# Sheet1.net
KiCad netlist of a schematic drawn in Altium Designer
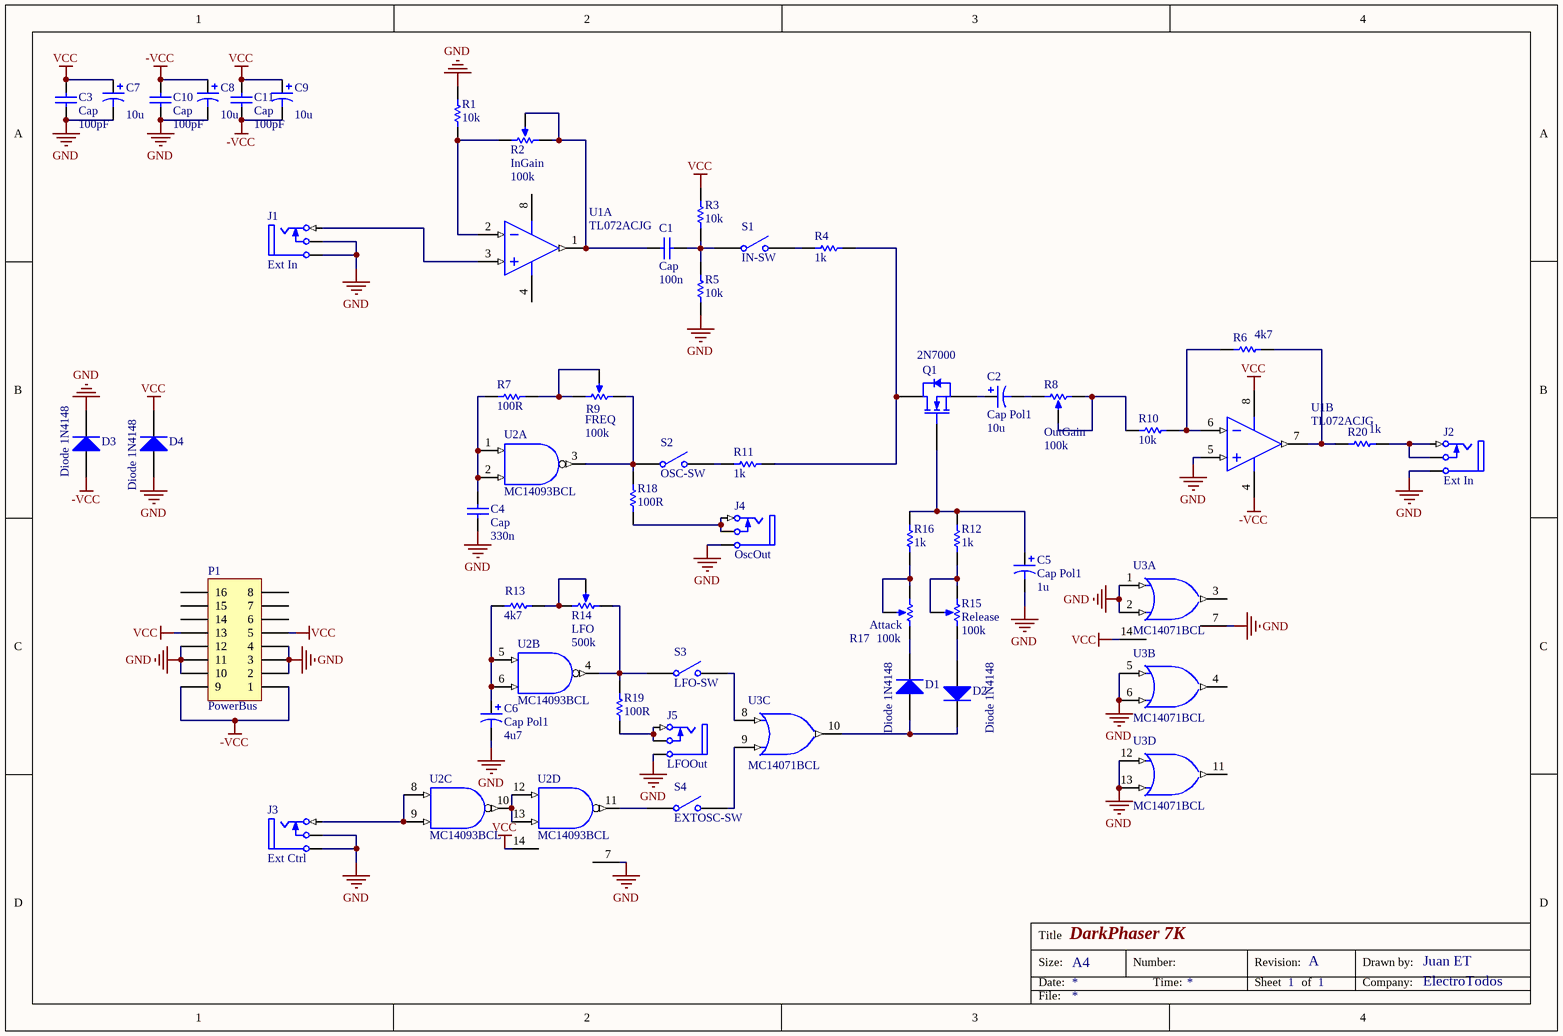
[diagram p0: Sheet1.SchDoc]

(export (version "E")
  (design (tool "Eeschema 10.0.6"))
  (components
    (comp (ref "C1")
      (value "Cap")
      (footprint "RAD-0.1")
      (description "Capacitor")
      (fields (field (name "ALTIUM_VALUE") "100n") (field (name "PUBLISHER") "Altium Limited"))
      (libsource (lib "Miscellaneous Devices") (part "Cap"))
    )
    (comp (ref "C2")
      (value "Cap Pol1")
      (footprint "Cap Radial")
      (description "Polarized Capacitor (Radial)")
      (fields (field (name "ALTIUM_VALUE") "10u") (field (name "PUBLISHER") "Altium Limited"))
      (libsource (lib "Miscellaneous Devices") (part "Cap Pol1"))
    )
    (comp (ref "C3")
      (value "Cap")
      (footprint "RAD-0.1")
      (description "Capacitor")
      (fields (field (name "ALTIUM_VALUE") "100pF") (field (name "PUBLISHER") "Altium Limited"))
      (libsource (lib "Miscellaneous Devices") (part "Cap"))
    )
    (comp (ref "C4")
      (value "Cap")
      (footprint "RAD-0.1")
      (description "Capacitor")
      (fields (field (name "ALTIUM_VALUE") "330n") (field (name "PUBLISHER") "Altium Limited"))
      (libsource (lib "Miscellaneous Devices") (part "Cap"))
    )
    (comp (ref "C5")
      (value "Cap Pol1")
      (footprint "Cap Radial")
      (description "Polarized Capacitor (Radial)")
      (fields (field (name "ALTIUM_VALUE") "1u") (field (name "PUBLISHER") "Altium Limited"))
      (libsource (lib "Miscellaneous Devices") (part "Cap Pol1"))
    )
    (comp (ref "C6")
      (value "Cap Pol1")
      (footprint "Cap Radial")
      (description "Polarized Capacitor (Radial)")
      (fields (field (name "ALTIUM_VALUE") "4u7") (field (name "PUBLISHER") "Altium Limited"))
      (libsource (lib "Miscellaneous Devices") (part "Cap Pol1"))
    )
    (comp (ref "C7")
      (value "10u")
      (footprint "Cap Radial")
      (description "Polarized Capacitor (Radial)")
      (fields (field (name "Comment") "Cap Pol1") (field (name "PUBLISHER") "Altium Limited"))
      (libsource (lib "Miscellaneous Devices") (part "Cap Pol1"))
    )
    (comp (ref "C8")
      (value "10u")
      (footprint "Cap Radial")
      (description "Polarized Capacitor (Radial)")
      (fields (field (name "Comment") "Cap Pol1") (field (name "PUBLISHER") "Altium Limited"))
      (libsource (lib "Miscellaneous Devices") (part "Cap Pol1"))
    )
    (comp (ref "C9")
      (value "10u")
      (footprint "Cap Radial")
      (description "Polarized Capacitor (Radial)")
      (fields (field (name "Comment") "Cap Pol1") (field (name "PUBLISHER") "Altium Limited"))
      (libsource (lib "Miscellaneous Devices") (part "Cap Pol1"))
    )
    (comp (ref "C10")
      (value "Cap")
      (footprint "RAD-0.1")
      (description "Capacitor")
      (fields (field (name "ALTIUM_VALUE") "100pF") (field (name "PUBLISHER") "Altium Limited"))
      (libsource (lib "Miscellaneous Devices") (part "Cap"))
    )
    (comp (ref "C11")
      (value "Cap")
      (footprint "RAD-0.1")
      (description "Capacitor")
      (fields (field (name "ALTIUM_VALUE") "100pF") (field (name "PUBLISHER") "Altium Limited"))
      (libsource (lib "Miscellaneous Devices") (part "Cap"))
    )
    (comp (ref "D1")
      (value "Diode 1N4148")
      (footprint "DO-35")
      (description "High Conductance Fast Diode")
      (fields (field (name "PUBLISHER") "Altium Limited"))
      (libsource (lib "Miscellaneous Devices") (part "Diode 1N4148"))
    )
    (comp (ref "D2")
      (value "Diode 1N4148")
      (footprint "DO-35")
      (description "High Conductance Fast Diode")
      (fields (field (name "PUBLISHER") "Altium Limited"))
      (libsource (lib "Miscellaneous Devices") (part "Diode 1N4148"))
    )
    (comp (ref "D3")
      (value "Diode 1N4148")
      (footprint "DO-35")
      (description "High Conductance Fast Diode")
      (fields (field (name "PUBLISHER") "Altium Limited"))
      (libsource (lib "Miscellaneous Devices") (part "Diode 1N4148"))
    )
    (comp (ref "D4")
      (value "Diode 1N4148")
      (footprint "DO-35")
      (description "High Conductance Fast Diode")
      (fields (field (name "PUBLISHER") "Altium Limited"))
      (libsource (lib "Miscellaneous Devices") (part "Diode 1N4148"))
    )
    (comp (ref "J1")
      (value "Ext In")
      (footprint "HDR1X3")
      (description "Jack Socket, 1/4\" [6.5mm], Thru-Hole, Vertical, 2-Conductor with Tip closed")
      (fields (field (name "PUBLISHER") "Altium Limited"))
      (libsource (lib "Miscellaneous Connectors") (part "Phonejack2 TN"))
    )
    (comp (ref "J2")
      (value "Ext In")
      (footprint "HDR1X3")
      (description "Jack Socket, 1/4\" [6.5mm], Thru-Hole, Vertical, 2-Conductor with Tip closed")
      (fields (field (name "PUBLISHER") "Altium Limited"))
      (libsource (lib "Miscellaneous Connectors") (part "Phonejack2 TN"))
    )
    (comp (ref "J3")
      (value "Ext Ctrl")
      (footprint "HDR1X3")
      (description "Jack Socket, 1/4\" [6.5mm], Thru-Hole, Vertical, 2-Conductor with Tip closed")
      (fields (field (name "PUBLISHER") "Altium Limited"))
      (libsource (lib "Miscellaneous Connectors") (part "Phonejack2 TN"))
    )
    (comp (ref "J4")
      (value "OscOut")
      (footprint "HDR1X3")
      (description "Jack Socket, 1/4\" [6.5mm], Thru-Hole, Vertical, 2-Conductor with Tip closed")
      (fields (field (name "PUBLISHER") "Altium Limited"))
      (libsource (lib "Miscellaneous Connectors") (part "Phonejack2 TN"))
    )
    (comp (ref "J5")
      (value "LFOOut")
      (footprint "HDR1X3")
      (description "Jack Socket, 1/4\" [6.5mm], Thru-Hole, Vertical, 2-Conductor with Tip closed")
      (fields (field (name "PUBLISHER") "Altium Limited"))
      (libsource (lib "Miscellaneous Connectors") (part "Phonejack2 TN"))
    )
    (comp (ref "P1")
      (value "PowerBus")
      (footprint "HDR2X8_CEN")
      (description "Header, 8-Pin, Dual row")
      (fields (field (name "PUBLISHER") "Altium Limited"))
      (libsource (lib "Miscellaneous Connectors") (part "Header 8X2A"))
    )
    (comp (ref "Q1")
      (value "2N7000")
      (footprint "SOT54")
      (description "N-channel Enhancement Mode Field-effect Transistor")
      (fields (field (name "PUBLISHER") "Altium Limited"))
      (libsource (lib "Philips Discrete MOSFET - Low Power") (part "2N7000"))
    )
    (comp (ref "R1")
      (value "10k")
      (footprint "AXIAL-0.3")
      (description "Resistor")
      (fields (field (name "PUBLISHER") "Altium Limited"))
      (libsource (lib "Miscellaneous Devices") (part "Res1"))
    )
    (comp (ref "R2")
      (value "InGain")
      (footprint "HDR1X3")
      (description "Potentiometer")
      (fields (field (name "ALTIUM_VALUE") "100k") (field (name "PUBLISHER") "Altium Limited"))
      (libsource (lib "Miscellaneous Devices") (part "RPot"))
    )
    (comp (ref "R3")
      (value "10k")
      (footprint "AXIAL-0.3")
      (description "Resistor")
      (fields (field (name "PUBLISHER") "Altium Limited"))
      (libsource (lib "Miscellaneous Devices") (part "Res1"))
    )
    (comp (ref "R4")
      (value "1k")
      (footprint "AXIAL-0.3")
      (description "Resistor")
      (fields (field (name "PUBLISHER") "Altium Limited"))
      (libsource (lib "Miscellaneous Devices") (part "Res1"))
    )
    (comp (ref "R5")
      (value "10k")
      (footprint "AXIAL-0.3")
      (description "Resistor")
      (fields (field (name "PUBLISHER") "Altium Limited"))
      (libsource (lib "Miscellaneous Devices") (part "Res1"))
    )
    (comp (ref "R6")
      (value "4k7")
      (footprint "AXIAL-0.3")
      (description "Resistor")
      (fields (field (name "PUBLISHER") "Altium Limited"))
      (libsource (lib "Miscellaneous Devices") (part "Res1"))
    )
    (comp (ref "R7")
      (value "100R")
      (footprint "AXIAL-0.3")
      (description "Resistor")
      (fields (field (name "PUBLISHER") "Altium Limited"))
      (libsource (lib "Miscellaneous Devices") (part "Res1"))
    )
    (comp (ref "R8")
      (value "OutGain")
      (footprint "HDR1X3")
      (description "Potentiometer")
      (fields (field (name "ALTIUM_VALUE") "100k") (field (name "PUBLISHER") "Altium Limited"))
      (libsource (lib "Miscellaneous Devices") (part "RPot"))
    )
    (comp (ref "R9")
      (value "FREQ")
      (footprint "HDR1X3")
      (description "Potentiometer")
      (fields (field (name "ALTIUM_VALUE") "100k") (field (name "PUBLISHER") "Altium Limited"))
      (libsource (lib "Miscellaneous Devices") (part "RPot"))
    )
    (comp (ref "R10")
      (value "10k")
      (footprint "AXIAL-0.3")
      (description "Resistor")
      (fields (field (name "PUBLISHER") "Altium Limited"))
      (libsource (lib "Miscellaneous Devices") (part "Res1"))
    )
    (comp (ref "R11")
      (value "1k")
      (footprint "AXIAL-0.3")
      (description "Resistor")
      (fields (field (name "PUBLISHER") "Altium Limited"))
      (libsource (lib "Miscellaneous Devices") (part "Res1"))
    )
    (comp (ref "R12")
      (value "1k")
      (footprint "AXIAL-0.3")
      (description "Resistor")
      (fields (field (name "PUBLISHER") "Altium Limited"))
      (libsource (lib "Miscellaneous Devices") (part "Res1"))
    )
    (comp (ref "R13")
      (value "4k7")
      (footprint "AXIAL-0.3")
      (description "Resistor")
      (fields (field (name "PUBLISHER") "Altium Limited"))
      (libsource (lib "Miscellaneous Devices") (part "Res1"))
    )
    (comp (ref "R14")
      (value "LFO")
      (footprint "HDR1X3")
      (description "Potentiometer")
      (fields (field (name "ALTIUM_VALUE") "500k") (field (name "PUBLISHER") "Altium Limited"))
      (libsource (lib "Miscellaneous Devices") (part "RPot"))
    )
    (comp (ref "R15")
      (value "Release")
      (footprint "HDR1X3")
      (description "Potentiometer")
      (fields (field (name "ALTIUM_VALUE") "100k") (field (name "PUBLISHER") "Altium Limited"))
      (libsource (lib "Miscellaneous Devices") (part "RPot"))
    )
    (comp (ref "R16")
      (value "1k")
      (footprint "AXIAL-0.3")
      (description "Resistor")
      (fields (field (name "PUBLISHER") "Altium Limited"))
      (libsource (lib "Miscellaneous Devices") (part "Res1"))
    )
    (comp (ref "R17")
      (value "Attack")
      (footprint "HDR1X3")
      (description "Potentiometer")
      (fields (field (name "ALTIUM_VALUE") "100k") (field (name "PUBLISHER") "Altium Limited"))
      (libsource (lib "Miscellaneous Devices") (part "RPot"))
    )
    (comp (ref "R18")
      (value "100R")
      (footprint "AXIAL-0.3")
      (description "Resistor")
      (fields (field (name "PUBLISHER") "Altium Limited"))
      (libsource (lib "Miscellaneous Devices") (part "Res1"))
    )
    (comp (ref "R19")
      (value "100R")
      (footprint "AXIAL-0.3")
      (description "Resistor")
      (fields (field (name "PUBLISHER") "Altium Limited"))
      (libsource (lib "Miscellaneous Devices") (part "Res1"))
    )
    (comp (ref "R20")
      (value "1k")
      (footprint "AXIAL-0.3")
      (description "Resistor")
      (fields (field (name "PUBLISHER") "Altium Limited"))
      (libsource (lib "Miscellaneous Devices") (part "Res1"))
    )
    (comp (ref "S1")
      (value "IN-SW")
      (footprint "PIN2")
      (description "Single-Pole, Single-Throw Switch")
      (fields (field (name "PUBLISHER") "Altium Limited"))
      (libsource (lib "Miscellaneous Devices") (part "SW-SPST"))
    )
    (comp (ref "S2")
      (value "OSC-SW")
      (footprint "PIN2")
      (description "Single-Pole, Single-Throw Switch")
      (fields (field (name "PUBLISHER") "Altium Limited"))
      (libsource (lib "Miscellaneous Devices") (part "SW-SPST"))
    )
    (comp (ref "S3")
      (value "LFO-SW")
      (footprint "PIN2")
      (description "Single-Pole, Single-Throw Switch")
      (fields (field (name "PUBLISHER") "Altium Limited"))
      (libsource (lib "Miscellaneous Devices") (part "SW-SPST"))
    )
    (comp (ref "S4")
      (value "EXTOSC-SW")
      (footprint "PIN2")
      (description "Single-Pole, Single-Throw Switch")
      (fields (field (name "PUBLISHER") "Altium Limited"))
      (libsource (lib "Miscellaneous Devices") (part "SW-SPST"))
    )
    (comp (ref "U1")
      (value "TL072ACJG")
      (footprint "693-02")
      (description "Low-Noise JFET-Input Operational Amplifier")
      (fields (field (name "PUBLISHER") "Altium Limited"))
      (libsource (lib "Motorola Amplifier Operational Amplifier") (part "TL072ACJG"))
    )
    (comp (ref "U2")
      (value "MC14093BCL")
      (footprint "632-08")
      (description "Quad 2-Input NAND Schmitt Trigger")
      (fields (field (name "PUBLISHER") "Altium Limited"))
      (libsource (lib "ON Semi Logic Gate") (part "MC14093BCL"))
    )
    (comp (ref "U3")
      (value "MC14071BCL")
      (footprint "632-08")
      (description "Quad 2-Input OR Gate")
      (fields (field (name "PUBLISHER") "Altium Limited"))
      (libsource (lib "ON Semi Logic Gate") (part "MC14071BCL"))
    )
  )
  (nets
    (net (code "1") (name "-VCC") (class "Default")
      (node (ref "C10") (pin "2") (pinfunction "2_2") (pintype "passive"))
      (node (ref "C11") (pin "1") (pinfunction "1_1") (pintype "passive"))
      (node (ref "C8") (pin "1") (pinfunction "1_1") (pintype "passive"))
      (node (ref "C9") (pin "2") (pinfunction "2_2") (pintype "passive"))
      (node (ref "D3") (pin "1") (pinfunction "A_1") (pintype "passive"))
      (node (ref "P1") (pin "1") (pinfunction "1_1") (pintype "passive"))
      (node (ref "P1") (pin "9") (pinfunction "9_9") (pintype "passive"))
      (node (ref "U1") (pin "4") (pinfunction "V-_4") (pintype "power_in"))
    )
    (net (code "2") (name "GND") (class "Default")
      (node (ref "C10") (pin "1") (pinfunction "1_1") (pintype "passive"))
      (node (ref "C3") (pin "2") (pinfunction "2_2") (pintype "passive"))
      (node (ref "C4") (pin "1") (pinfunction "1_1") (pintype "passive"))
      (node (ref "C5") (pin "2") (pinfunction "2_2") (pintype "passive"))
      (node (ref "C6") (pin "2") (pinfunction "2_2") (pintype "passive"))
      (node (ref "C7") (pin "2") (pinfunction "2_2") (pintype "passive"))
      (node (ref "C8") (pin "2") (pinfunction "2_2") (pintype "passive"))
      (node (ref "D3") (pin "2") (pinfunction "K_2") (pintype "passive"))
      (node (ref "D4") (pin "1") (pinfunction "A_1") (pintype "passive"))
      (node (ref "J1") (pin "2") (pinfunction "TN_2") (pintype "passive"))
      (node (ref "J1") (pin "5") (pinfunction "S_5") (pintype "power_in"))
      (node (ref "J2") (pin "5") (pinfunction "S_5") (pintype "power_in"))
      (node (ref "J3") (pin "2") (pinfunction "TN_2") (pintype "passive"))
      (node (ref "J3") (pin "5") (pinfunction "S_5") (pintype "power_in"))
      (node (ref "J4") (pin "5") (pinfunction "S_5") (pintype "power_in"))
      (node (ref "J5") (pin "5") (pinfunction "S_5") (pintype "power_in"))
      (node (ref "P1") (pin "10") (pinfunction "10_10") (pintype "passive"))
      (node (ref "P1") (pin "11") (pinfunction "11_11") (pintype "passive"))
      (node (ref "P1") (pin "12") (pinfunction "12_12") (pintype "passive"))
      (node (ref "P1") (pin "2") (pinfunction "2_2") (pintype "passive"))
      (node (ref "P1") (pin "3") (pinfunction "3_3") (pintype "passive"))
      (node (ref "P1") (pin "4") (pinfunction "4_4") (pintype "passive"))
      (node (ref "R1") (pin "2") (pinfunction "2_2") (pintype "passive"))
      (node (ref "R5") (pin "2") (pinfunction "2_2") (pintype "passive"))
      (node (ref "U1") (pin "5") (pinfunction "IN+_5") (pintype "input"))
      (node (ref "U2") (pin "7") (pinfunction "GND_7") (pintype "power_in"))
      (node (ref "U3") (pin "1") (pinfunction "A_1") (pintype "input"))
      (node (ref "U3") (pin "12") (pinfunction "A_12") (pintype "input"))
      (node (ref "U3") (pin "13") (pinfunction "B_13") (pintype "input"))
      (node (ref "U3") (pin "2") (pinfunction "B_2") (pintype "input"))
      (node (ref "U3") (pin "5") (pinfunction "A_5") (pintype "input"))
      (node (ref "U3") (pin "6") (pinfunction "B_6") (pintype "input"))
      (node (ref "U3") (pin "7") (pinfunction "GND_7") (pintype "power_in"))
    )
    (net (code "3") (name "Net-(D1-A)") (class "Default")
      (node (ref "D1") (pin "1") (pinfunction "A_1") (pintype "passive"))
      (node (ref "D2") (pin "2") (pinfunction "K_2") (pintype "passive"))
      (node (ref "U3") (pin "10") (pinfunction "Y_10") (pintype "output"))
    )
    (net (code "4") (name "Net-(D1-K)") (class "Default")
      (node (ref "D1") (pin "2") (pinfunction "K_2") (pintype "passive"))
      (node (ref "R17") (pin "2") (pinfunction "BOT_2") (pintype "passive"))
    )
    (net (code "5") (name "Net-(D2-A)") (class "Default")
      (node (ref "D2") (pin "1") (pinfunction "A_1") (pintype "passive"))
      (node (ref "R15") (pin "2") (pinfunction "BOT_2") (pintype "passive"))
    )
    (net (code "6") (name "Net-(J1-T)") (class "Default")
      (node (ref "J1") (pin "1") (pinfunction "T_1") (pintype "input"))
      (node (ref "U1") (pin "3") (pinfunction "IN+_3") (pintype "input"))
    )
    (net (code "7") (name "Net-(J2-T)") (class "Default")
      (node (ref "J2") (pin "1") (pinfunction "T_1") (pintype "input"))
      (node (ref "J2") (pin "2") (pinfunction "TN_2") (pintype "passive"))
      (node (ref "R20") (pin "1") (pinfunction "1_1") (pintype "passive"))
    )
    (net (code "8") (name "Net-(J3-T)") (class "Default")
      (node (ref "J3") (pin "1") (pinfunction "T_1") (pintype "input"))
      (node (ref "U2") (pin "8") (pinfunction "A_8") (pintype "input"))
      (node (ref "U2") (pin "9") (pinfunction "B_9") (pintype "input"))
    )
    (net (code "9") (name "Net-(J4-T)") (class "Default")
      (node (ref "J4") (pin "1") (pinfunction "T_1") (pintype "input"))
      (node (ref "J4") (pin "2") (pinfunction "TN_2") (pintype "passive"))
      (node (ref "R18") (pin "1") (pinfunction "1_1") (pintype "passive"))
    )
    (net (code "10") (name "Net-(J5-T)") (class "Default")
      (node (ref "J5") (pin "1") (pinfunction "T_1") (pintype "input"))
      (node (ref "J5") (pin "2") (pinfunction "TN_2") (pintype "passive"))
      (node (ref "R19") (pin "1") (pinfunction "1_1") (pintype "passive"))
    )
    (net (code "11") (name "Net-(Q1-D)") (class "Default")
      (node (ref "Q1") (pin "1") (pinfunction "D_1") (pintype "passive"))
      (node (ref "R11") (pin "2") (pinfunction "2_2") (pintype "passive"))
      (node (ref "R4") (pin "2") (pinfunction "2_2") (pintype "passive"))
    )
    (net (code "12") (name "Net-(Q1-G)") (class "Default")
      (node (ref "C5") (pin "1") (pinfunction "1_1") (pintype "passive"))
      (node (ref "Q1") (pin "2") (pinfunction "G_2") (pintype "passive"))
      (node (ref "R12") (pin "2") (pinfunction "2_2") (pintype "passive"))
      (node (ref "R16") (pin "2") (pinfunction "2_2") (pintype "passive"))
    )
    (net (code "13") (name "Net-(Q1-S)") (class "Default")
      (node (ref "C2") (pin "1") (pinfunction "1_1") (pintype "passive"))
      (node (ref "Q1") (pin "3") (pinfunction "S_3") (pintype "passive"))
    )
    (net (code "14") (name "Net-(R2-BOT)") (class "Default")
      (node (ref "R1") (pin "1") (pinfunction "1_1") (pintype "passive"))
      (node (ref "R2") (pin "2") (pinfunction "BOT_2") (pintype "passive"))
      (node (ref "U1") (pin "2") (pinfunction "IN-_2") (pintype "input"))
    )
    (net (code "15") (name "Net-(R2-TAP)") (class "Default")
      (node (ref "C1") (pin "2") (pinfunction "2_2") (pintype "passive"))
      (node (ref "R2") (pin "1") (pinfunction "TOP_1") (pintype "passive"))
      (node (ref "R2") (pin "3") (pinfunction "TAP_3") (pintype "passive"))
      (node (ref "U1") (pin "1") (pinfunction "OUT_1") (pintype "output"))
    )
    (net (code "16") (name "Net-(R8-BOT)") (class "Default")
      (node (ref "R10") (pin "2") (pinfunction "2_2") (pintype "passive"))
      (node (ref "R8") (pin "2") (pinfunction "BOT_2") (pintype "passive"))
      (node (ref "R8") (pin "3") (pinfunction "TAP_3") (pintype "passive"))
    )
    (net (code "17") (name "Net-(R8-TOP)") (class "Default")
      (node (ref "C2") (pin "2") (pinfunction "2_2") (pintype "passive"))
      (node (ref "R8") (pin "1") (pinfunction "TOP_1") (pintype "passive"))
    )
    (net (code "18") (name "Net-(R9-BOT)") (class "Default")
      (node (ref "R7") (pin "2") (pinfunction "2_2") (pintype "passive"))
      (node (ref "R9") (pin "2") (pinfunction "BOT_2") (pintype "passive"))
      (node (ref "R9") (pin "3") (pinfunction "TAP_3") (pintype "passive"))
    )
    (net (code "19") (name "Net-(R9-TOP)") (class "Default")
      (node (ref "R18") (pin "2") (pinfunction "2_2") (pintype "passive"))
      (node (ref "R9") (pin "1") (pinfunction "TOP_1") (pintype "passive"))
      (node (ref "S2") (pin "1") (pinfunction "COMMON_1") (pintype "passive"))
      (node (ref "U2") (pin "3") (pinfunction "~{Y}_3") (pintype "output"))
    )
    (net (code "20") (name "Net-(R14-BOT)") (class "Default")
      (node (ref "R13") (pin "2") (pinfunction "2_2") (pintype "passive"))
      (node (ref "R14") (pin "2") (pinfunction "BOT_2") (pintype "passive"))
      (node (ref "R14") (pin "3") (pinfunction "TAP_3") (pintype "passive"))
    )
    (net (code "21") (name "Net-(R14-TOP)") (class "Default")
      (node (ref "R14") (pin "1") (pinfunction "TOP_1") (pintype "passive"))
      (node (ref "R19") (pin "2") (pinfunction "2_2") (pintype "passive"))
      (node (ref "S3") (pin "1") (pinfunction "COMMON_1") (pintype "passive"))
      (node (ref "U2") (pin "4") (pinfunction "~{Y}_4") (pintype "output"))
    )
    (net (code "22") (name "Net-(R15-TAP)") (class "Default")
      (node (ref "R12") (pin "1") (pinfunction "1_1") (pintype "passive"))
      (node (ref "R15") (pin "1") (pinfunction "TOP_1") (pintype "passive"))
      (node (ref "R15") (pin "3") (pinfunction "TAP_3") (pintype "passive"))
    )
    (net (code "23") (name "Net-(R17-TAP)") (class "Default")
      (node (ref "R16") (pin "1") (pinfunction "1_1") (pintype "passive"))
      (node (ref "R17") (pin "1") (pinfunction "TOP_1") (pintype "passive"))
      (node (ref "R17") (pin "3") (pinfunction "TAP_3") (pintype "passive"))
    )
    (net (code "24") (name "Net-(S1-COMMON)") (class "Default")
      (node (ref "C1") (pin "1") (pinfunction "1_1") (pintype "passive"))
      (node (ref "R3") (pin "2") (pinfunction "2_2") (pintype "passive"))
      (node (ref "R5") (pin "1") (pinfunction "1_1") (pintype "passive"))
      (node (ref "S1") (pin "1") (pinfunction "COMMON_1") (pintype "passive"))
    )
    (net (code "25") (name "Net-(S1-NO)") (class "Default")
      (node (ref "R4") (pin "1") (pinfunction "1_1") (pintype "passive"))
      (node (ref "S1") (pin "2") (pinfunction "NO_2") (pintype "passive"))
    )
    (net (code "26") (name "Net-(S2-NO)") (class "Default")
      (node (ref "R11") (pin "1") (pinfunction "1_1") (pintype "passive"))
      (node (ref "S2") (pin "2") (pinfunction "NO_2") (pintype "passive"))
    )
    (net (code "27") (name "Net-(S3-NO)") (class "Default")
      (node (ref "S3") (pin "2") (pinfunction "NO_2") (pintype "passive"))
      (node (ref "U3") (pin "8") (pinfunction "A_8") (pintype "input"))
    )
    (net (code "28") (name "Net-(S4-COMMON)") (class "Default")
      (node (ref "S4") (pin "1") (pinfunction "COMMON_1") (pintype "passive"))
      (node (ref "U2") (pin "11") (pinfunction "~{Y}_11") (pintype "output"))
    )
    (net (code "29") (name "Net-(S4-NO)") (class "Default")
      (node (ref "S4") (pin "2") (pinfunction "NO_2") (pintype "passive"))
      (node (ref "U3") (pin "9") (pinfunction "B_9") (pintype "input"))
    )
    (net (code "30") (name "Net-(U1B-IN-)") (class "Default")
      (node (ref "R10") (pin "1") (pinfunction "1_1") (pintype "passive"))
      (node (ref "R6") (pin "2") (pinfunction "2_2") (pintype "passive"))
      (node (ref "U1") (pin "6") (pinfunction "IN-_6") (pintype "input"))
    )
    (net (code "31") (name "Net-(U1B-OUT)") (class "Default")
      (node (ref "R20") (pin "2") (pinfunction "2_2") (pintype "passive"))
      (node (ref "R6") (pin "1") (pinfunction "1_1") (pintype "passive"))
      (node (ref "U1") (pin "7") (pinfunction "OUT_7") (pintype "output"))
    )
    (net (code "32") (name "Net-(U2A-A)") (class "Default")
      (node (ref "C4") (pin "2") (pinfunction "2_2") (pintype "passive"))
      (node (ref "R7") (pin "1") (pinfunction "1_1") (pintype "passive"))
      (node (ref "U2") (pin "1") (pinfunction "A_1") (pintype "input"))
      (node (ref "U2") (pin "2") (pinfunction "B_2") (pintype "input"))
    )
    (net (code "33") (name "Net-(U2B-A)") (class "Default")
      (node (ref "C6") (pin "1") (pinfunction "1_1") (pintype "passive"))
      (node (ref "R13") (pin "1") (pinfunction "1_1") (pintype "passive"))
      (node (ref "U2") (pin "5") (pinfunction "A_5") (pintype "input"))
      (node (ref "U2") (pin "6") (pinfunction "B_6") (pintype "input"))
    )
    (net (code "34") (name "Net-(U2C-~{Y})") (class "Default")
      (node (ref "U2") (pin "10") (pinfunction "~{Y}_10") (pintype "output"))
      (node (ref "U2") (pin "12") (pinfunction "A_12") (pintype "input"))
      (node (ref "U2") (pin "13") (pinfunction "B_13") (pintype "input"))
    )
    (net (code "35") (name "VCC") (class "Default")
      (node (ref "C11") (pin "2") (pinfunction "2_2") (pintype "passive"))
      (node (ref "C3") (pin "1") (pinfunction "1_1") (pintype "passive"))
      (node (ref "C7") (pin "1") (pinfunction "1_1") (pintype "passive"))
      (node (ref "C9") (pin "1") (pinfunction "1_1") (pintype "passive"))
      (node (ref "D4") (pin "2") (pinfunction "K_2") (pintype "passive"))
      (node (ref "P1") (pin "13") (pinfunction "13_13") (pintype "passive"))
      (node (ref "P1") (pin "5") (pinfunction "5_5") (pintype "passive"))
      (node (ref "R3") (pin "1") (pinfunction "1_1") (pintype "passive"))
      (node (ref "U1") (pin "8") (pinfunction "V+_8") (pintype "power_in"))
      (node (ref "U2") (pin "14") (pinfunction "VDD_14") (pintype "power_in"))
      (node (ref "U3") (pin "14") (pinfunction "VDD_14") (pintype "power_in"))
    )
    (net (code "36") (name "unconnected-(P1-Pad6)") (class "Default")
      (node (ref "P1") (pin "6") (pinfunction "6_6") (pintype "passive"))
    )
    (net (code "37") (name "unconnected-(P1-Pad7)") (class "Default")
      (node (ref "P1") (pin "7") (pinfunction "7_7") (pintype "passive"))
    )
    (net (code "38") (name "unconnected-(P1-Pad8)") (class "Default")
      (node (ref "P1") (pin "8") (pinfunction "8_8") (pintype "passive"))
    )
    (net (code "39") (name "unconnected-(P1-Pad14)") (class "Default")
      (node (ref "P1") (pin "14") (pinfunction "14_14") (pintype "passive"))
    )
    (net (code "40") (name "unconnected-(P1-Pad15)") (class "Default")
      (node (ref "P1") (pin "15") (pinfunction "15_15") (pintype "passive"))
    )
    (net (code "41") (name "unconnected-(P1-Pad16)") (class "Default")
      (node (ref "P1") (pin "16") (pinfunction "16_16") (pintype "passive"))
    )
    (net (code "42") (name "unconnected-(U1A-V+-Pad8)") (class "Default")
      (node (ref "U1") (pin "8") (pinfunction "V+_8") (pintype "power_in"))
    )
    (net (code "43") (name "unconnected-(U1A-V--Pad4)") (class "Default")
      (node (ref "U1") (pin "4") (pinfunction "V-_4") (pintype "power_in"))
    )
    (net (code "44") (name "unconnected-(U3A-Y-Pad3)") (class "Default")
      (node (ref "U3") (pin "3") (pinfunction "Y_3") (pintype "output"))
    )
    (net (code "45") (name "unconnected-(U3B-Y-Pad4)") (class "Default")
      (node (ref "U3") (pin "4") (pinfunction "Y_4") (pintype "output"))
    )
    (net (code "46") (name "unconnected-(U3D-Y-Pad11)") (class "Default")
      (node (ref "U3") (pin "11") (pinfunction "Y_11") (pintype "output"))
    )
  )
)
